# Supply_LDOs.net
KiCad netlist of a schematic drawn in Altium Designer
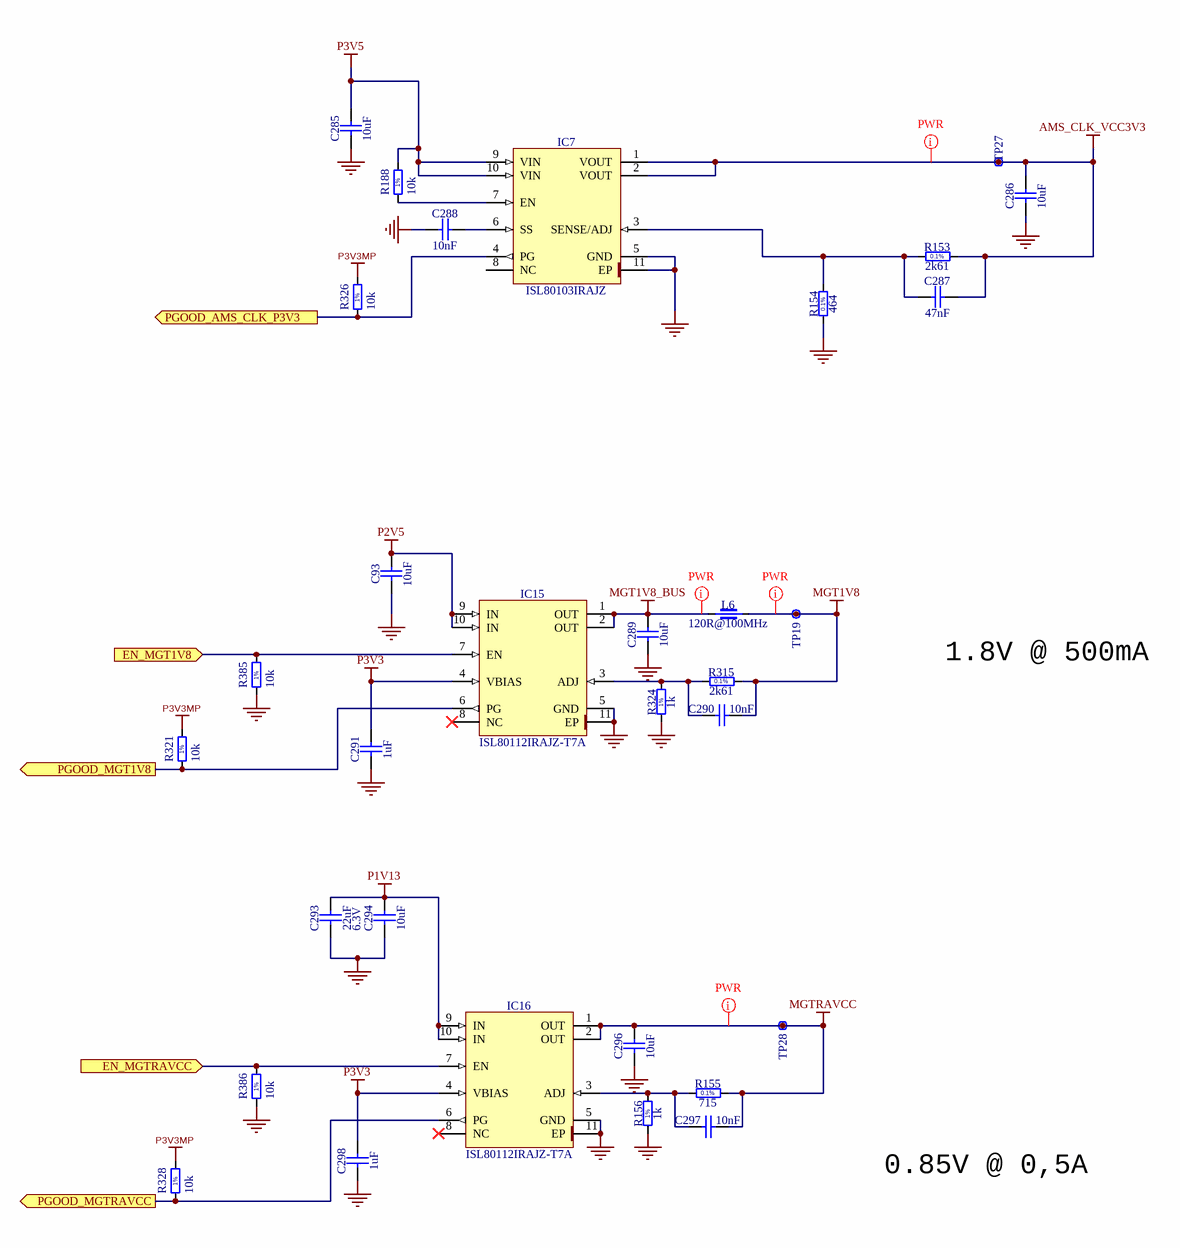
[diagram p0: Supply_LDOs.SchDoc]

(export (version "E")
  (design (tool "Eeschema 10.0.6"))
  (components
    (comp (ref "C93")
      (value "10uF")
      (footprint "CAPC1608X80N")
      (description "Non-polarised capacitor")
      (fields
        (field (name "PART NUMBER") "CC0603_10UF_10V_10%_X5R")
        (field (name "VOLTAGE") "10V")
        (field (name "AUTHOR") "CERN DEM JLC")
      )
      (libsource (lib "Capacitors") (part "Capacitor - non polarized"))
    )
    (comp (ref "C285")
      (value "10uF")
      (footprint "CAPC1608X80N")
      (description "Non-polarised capacitor")
      (fields
        (field (name "PART NUMBER") "CC0603_10UF_10V_10%_X5R")
        (field (name "VOLTAGE") "10V")
        (field (name "AUTHOR") "CERN DEM JLC")
      )
      (libsource (lib "Capacitors") (part "Capacitor - non polarized"))
    )
    (comp (ref "C286")
      (value "10uF")
      (footprint "CAPC1608X80N")
      (description "Non-polarised capacitor")
      (fields
        (field (name "PART NUMBER") "CC0603_10UF_10V_10%_X5R")
        (field (name "VOLTAGE") "10V")
        (field (name "AUTHOR") "CERN DEM JLC")
      )
      (libsource (lib "Capacitors") (part "Capacitor - non polarized"))
    )
    (comp (ref "C287")
      (value "47nF")
      (footprint "CAPC1005X55N")
      (description "Non-polarised capacitor")
      (fields
        (field (name "PART NUMBER") "CC0402_47NF_16V_10%_X7R")
        (field (name "VOLTAGE") "16V")
        (field (name "AUTHOR") "CERN DEM JLC")
      )
      (libsource (lib "Capacitors") (part "Capacitor - non polarized"))
    )
    (comp (ref "C288")
      (value "10nF")
      (footprint "CAPC1005X55N")
      (description "Non-polarised capacitor")
      (fields
        (field (name "PART NUMBER") "CC0402_10NF_16V_10%_X7R")
        (field (name "VOLTAGE") "16V")
        (field (name "AUTHOR") "CERN DEM JLC")
      )
      (libsource (lib "Capacitors") (part "Capacitor - non polarized"))
    )
    (comp (ref "C289")
      (value "10uF")
      (footprint "CAPC1608X80N")
      (description "Non-polarised capacitor")
      (fields
        (field (name "PART NUMBER") "CC0603_10UF_10V_10%_X5R")
        (field (name "VOLTAGE") "10V")
        (field (name "AUTHOR") "CERN DEM JLC")
      )
      (libsource (lib "Capacitors") (part "Capacitor - non polarized"))
    )
    (comp (ref "C290")
      (value "10nF")
      (footprint "CAPC1005X55N")
      (description "Non-polarised capacitor")
      (fields
        (field (name "PART NUMBER") "CC0402_10NF_25V_10%_X7R")
        (field (name "VOLTAGE") "25V")
        (field (name "AUTHOR") "CERN DEM JLC")
      )
      (libsource (lib "Capacitors") (part "Capacitor - non polarized"))
    )
    (comp (ref "C291")
      (value "1uF")
      (footprint "CAPC1005X55N")
      (description "Non-polarised capacitor")
      (fields
        (field (name "PART NUMBER") "CC0402_1UF_16V_10%_X5R")
        (field (name "VOLTAGE") "16V")
        (field (name "AUTHOR") "CERN DEM JLC")
      )
      (libsource (lib "Capacitors") (part "Capacitor - non polarized"))
    )
    (comp (ref "C293")
      (value "22uF")
      (footprint "CAPC1709X100N")
      (description "Non-polarised capacitor")
      (fields
        (field (name "PART NUMBER") "CC0603_22UF_6.3V_20%_X5R")
        (field (name "VOLTAGE") "6.3V")
        (field (name "TOLERANCE") "±20%")
        (field (name "AUTHOR") "CERN DEM JLC")
      )
      (libsource (lib "Capacitors") (part "Capacitor - non polarized"))
    )
    (comp (ref "C294")
      (value "10uF")
      (footprint "CAPC1608X80N")
      (description "Non-polarised capacitor")
      (fields
        (field (name "PART NUMBER") "CC0603_10UF_10V_10%_X5R")
        (field (name "VOLTAGE") "10V")
        (field (name "AUTHOR") "CERN DEM JLC")
      )
      (libsource (lib "Capacitors") (part "Capacitor - non polarized"))
    )
    (comp (ref "C296")
      (value "10uF")
      (footprint "CAPC1608X80N")
      (description "Non-polarised capacitor")
      (fields
        (field (name "PART NUMBER") "CC0603_10UF_10V_10%_X5R")
        (field (name "VOLTAGE") "10V")
        (field (name "AUTHOR") "CERN DEM JLC")
      )
      (libsource (lib "Capacitors") (part "Capacitor - non polarized"))
    )
    (comp (ref "C297")
      (value "10nF")
      (footprint "CAPC1005X55N")
      (description "Non-polarised capacitor")
      (fields
        (field (name "PART NUMBER") "CC0402_10NF_25V_10%_X7R")
        (field (name "VOLTAGE") "25V")
        (field (name "AUTHOR") "CERN DEM JLC")
      )
      (libsource (lib "Capacitors") (part "Capacitor - non polarized"))
    )
    (comp (ref "C298")
      (value "1uF")
      (footprint "CAPC1005X55N")
      (description "Non-polarised capacitor")
      (fields
        (field (name "PART NUMBER") "CC0402_1UF_16V_10%_X5R")
        (field (name "VOLTAGE") "16V")
        (field (name "AUTHOR") "CERN DEM JLC")
      )
      (libsource (lib "Capacitors") (part "Capacitor - non polarized"))
    )
    (comp (ref "IC7")
      (value "ISL80103IRAJZ")
      (footprint "RENESAS_L10.3X3")
      (description "High Performance 3A Linear Regulators")
      (fields (field (name "MANUFACTURER") "RENESAS ELECTRONICS") (field (name "AUTHOR") "CERN DEM MR"))
      (libsource (lib "ICs And Semiconductors") (part "ISL80103"))
    )
    (comp (ref "IC15")
      (value "ISL80112IRAJZ-T7A")
      (footprint "RENESAS_L10.3X3")
      (description "Ultra Low Dropout Low Input Voltage NMOS LDO Regulator")
      (fields (field (name "MANUFACTURER") "RENESAS ELECTRONICS") (field (name "AUTHOR") "CERN DEM JLC"))
      (libsource (lib "ICs And Semiconductors") (part "ISL8011x"))
    )
    (comp (ref "IC16")
      (value "ISL80112IRAJZ-T7A")
      (footprint "RENESAS_L10.3X3")
      (description "Ultra Low Dropout Low Input Voltage NMOS LDO Regulator")
      (fields (field (name "MANUFACTURER") "RENESAS ELECTRONICS") (field (name "AUTHOR") "CERN DEM JLC"))
      (libsource (lib "ICs And Semiconductors") (part "ISL8011x"))
    )
    (comp (ref "L6")
      (value "120R@100MHz")
      (footprint "INDC1608X95N")
      (fields
        (field (name "MANUFACTURER PART NUMBER") "BLM18PG121SN1D")
        (field (name "MANUFACTURER") "MURATA")
        (field (name "PART NUMBER") "IND0603_MURATA_BLM18PG121SN1D")
        (field (name "AUTHOR") "CERN DEM BC")
      )
      (libsource (lib "Inductors & Transformers") (part "Ferrite Bead"))
    )
    (comp (ref "R153")
      (value "2k61")
      (footprint "RESC1608X55N")
      (description "Resistor - 0.1%")
      (fields
        (field (name "PART NUMBER") "R0603_2K61_0.1%_0.063W_10PPM")
        (field (name "POWER") "0.063W")
        (field (name "AUTHOR") "CERN DEM JLC")
      )
      (libsource (lib "Resistors") (part "Resistor - 0.1%"))
    )
    (comp (ref "R154")
      (value "464")
      (footprint "RESC1608X55N")
      (description "Resistor - 0.1%")
      (fields
        (field (name "PART NUMBER") "R0603_464R_0.1%_0.063W_10PPM")
        (field (name "POWER") "0.063W")
        (field (name "AUTHOR") "CERN DEM JLC")
      )
      (libsource (lib "Resistors") (part "Resistor - 0.1%"))
    )
    (comp (ref "R155")
      (value "715")
      (footprint "RESC1608X55N")
      (description "Resistor - 0.1%")
      (fields
        (field (name "PART NUMBER") "R0603_715R_0.1%_0.063W_10PPM")
        (field (name "POWER") "0.063W")
        (field (name "AUTHOR") "CERN DEM JLC")
      )
      (libsource (lib "Resistors") (part "Resistor - 0.1%"))
    )
    (comp (ref "R156")
      (value "1k")
      (footprint "RESC1608X55N")
      (description "Resistor - 1%")
      (fields
        (field (name "PART NUMBER") "R0603_1K_1%_0.1W_100PPM")
        (field (name "POWER") "0.1W")
        (field (name "AUTHOR") "CERN DEM JLC")
      )
      (libsource (lib "Resistors") (part "Resistor - 1%"))
    )
    (comp (ref "R188")
      (value "10k")
      (footprint "RESC1005X40N")
      (description "Resistor - 1%")
      (fields
        (field (name "MANUFACTURER PART NUMBER") "R0402_10K_1%_0.0625W_100PPM")
        (field (name "MANUFACTURER") "GENERIC")
        (field (name "AUTHOR") "CERN DEM JLC")
      )
      (libsource (lib "Resistors") (part "Resistor - 1%"))
    )
    (comp (ref "R315")
      (value "2k61")
      (footprint "RESC1608X55N")
      (description "Resistor - 0.1%")
      (fields
        (field (name "PART NUMBER") "R0603_2K61_0.1%_0.063W_10PPM")
        (field (name "POWER") "0.063W")
        (field (name "AUTHOR") "CERN DEM JLC")
      )
      (libsource (lib "Resistors") (part "Resistor - 0.1%"))
    )
    (comp (ref "R321")
      (value "10k")
      (footprint "RESC1005X40N")
      (description "Resistor - 1%")
      (fields
        (field (name "MANUFACTURER PART NUMBER") "R0402_10K_1%_0.0625W_100PPM")
        (field (name "MANUFACTURER") "GENERIC")
        (field (name "AUTHOR") "CERN DEM JLC")
      )
      (libsource (lib "Resistors") (part "Resistor - 1%"))
    )
    (comp (ref "R324")
      (value "1k")
      (footprint "RESC1608X55N")
      (description "Resistor - 1%")
      (fields
        (field (name "PART NUMBER") "R0603_1K_1%_0.1W_100PPM")
        (field (name "POWER") "0.1W")
        (field (name "AUTHOR") "CERN DEM JLC")
      )
      (libsource (lib "Resistors") (part "Resistor - 1%"))
    )
    (comp (ref "R326")
      (value "10k")
      (footprint "RESC1005X40N")
      (description "Resistor - 1%")
      (fields
        (field (name "MANUFACTURER PART NUMBER") "R0402_10K_1%_0.0625W_100PPM")
        (field (name "MANUFACTURER") "GENERIC")
        (field (name "AUTHOR") "CERN DEM JLC")
      )
      (libsource (lib "Resistors") (part "Resistor - 1%"))
    )
    (comp (ref "R328")
      (value "10k")
      (footprint "RESC1005X40N")
      (description "Resistor - 1%")
      (fields
        (field (name "MANUFACTURER PART NUMBER") "R0402_10K_1%_0.0625W_100PPM")
        (field (name "MANUFACTURER") "GENERIC")
        (field (name "AUTHOR") "CERN DEM JLC")
      )
      (libsource (lib "Resistors") (part "Resistor - 1%"))
    )
    (comp (ref "R385")
      (value "10k")
      (footprint "RESC1005X40N")
      (description "Resistor - 1%")
      (fields
        (field (name "MANUFACTURER PART NUMBER") "R0402_10K_1%_0.0625W_100PPM")
        (field (name "MANUFACTURER") "GENERIC")
        (field (name "AUTHOR") "CERN DEM JLC")
      )
      (libsource (lib "Resistors") (part "Resistor - 1%"))
    )
    (comp (ref "R386")
      (value "10k")
      (footprint "RESC1005X40N")
      (description "Resistor - 1%")
      (fields
        (field (name "MANUFACTURER PART NUMBER") "R0402_10K_1%_0.0625W_100PPM")
        (field (name "MANUFACTURER") "GENERIC")
        (field (name "AUTHOR") "CERN DEM JLC")
      )
      (libsource (lib "Resistors") (part "Resistor - 1%"))
    )
    (comp (ref "TP19")
      (value "Test Point")
      (footprint "TPS127")
      (fields (field (name "PART NUMBER") "SMD_PAD_1.27X1.27MM") (field (name "AUTHOR") "CERN DEM JLC"))
      (libsource (lib "Eletro-mechanical") (part "Test Point"))
    )
    (comp (ref "TP27")
      (value "Test Point")
      (footprint "TPS127")
      (fields (field (name "PART NUMBER") "SMD_PAD_1.27X1.27MM") (field (name "AUTHOR") "CERN DEM JLC"))
      (libsource (lib "Eletro-mechanical") (part "Test Point"))
    )
    (comp (ref "TP28")
      (value "Test Point")
      (footprint "TPS127")
      (fields (field (name "PART NUMBER") "SMD_PAD_1.27X1.27MM") (field (name "AUTHOR") "CERN DEM JLC"))
      (libsource (lib "Eletro-mechanical") (part "Test Point"))
    )
  )
  (nets
    (net (code "1") (name "/EN_MGT1V8") (class "Default")
      (node (ref "IC15") (pin "7") (pinfunction "EN_7") (pintype "input"))
      (node (ref "R385") (pin "2") (pinfunction "2_2") (pintype "passive"))
    )
    (net (code "2") (name "/EN_MGTRAVCC") (class "Default")
      (node (ref "IC16") (pin "7") (pinfunction "EN_7") (pintype "input"))
      (node (ref "R386") (pin "2") (pinfunction "2_2") (pintype "passive"))
    )
    (net (code "3") (name "/PGOOD_AMS_CLK_P3V3") (class "Default")
      (node (ref "IC7") (pin "4") (pinfunction "PG_4") (pintype "output"))
      (node (ref "R326") (pin "1") (pinfunction "1_1") (pintype "passive"))
    )
    (net (code "4") (name "/PGOOD_MGT1V8") (class "Default")
      (node (ref "IC15") (pin "6") (pinfunction "PG_6") (pintype "output"))
      (node (ref "R321") (pin "1") (pinfunction "1_1") (pintype "passive"))
    )
    (net (code "5") (name "/PGOOD_MGTRAVCC") (class "Default")
      (node (ref "IC16") (pin "6") (pinfunction "PG_6") (pintype "output"))
      (node (ref "R328") (pin "1") (pinfunction "1_1") (pintype "passive"))
    )
    (net (code "6") (name "AMS_CLK_VCC3V3") (class "Default")
      (node (ref "C286") (pin "2") (pinfunction "2_2") (pintype "passive"))
      (node (ref "C287") (pin "2") (pinfunction "2_2") (pintype "passive"))
      (node (ref "IC7") (pin "1") (pinfunction "VOUT_1") (pintype "power_in"))
      (node (ref "IC7") (pin "2") (pinfunction "VOUT_2") (pintype "power_in"))
      (node (ref "R153") (pin "2") (pinfunction "2_2") (pintype "passive"))
      (node (ref "TP27") (pin "1") (pinfunction "1_1") (pintype "bidirectional"))
    )
    (net (code "7") (name "GND") (class "Default")
      (node (ref "C285") (pin "1") (pinfunction "1_1") (pintype "passive"))
      (node (ref "C286") (pin "1") (pinfunction "1_1") (pintype "passive"))
      (node (ref "C288") (pin "1") (pinfunction "1_1") (pintype "passive"))
      (node (ref "C289") (pin "1") (pinfunction "1_1") (pintype "passive"))
      (node (ref "C291") (pin "1") (pinfunction "1_1") (pintype "passive"))
      (node (ref "C293") (pin "1") (pinfunction "1_1") (pintype "passive"))
      (node (ref "C294") (pin "1") (pinfunction "1_1") (pintype "passive"))
      (node (ref "C296") (pin "1") (pinfunction "1_1") (pintype "passive"))
      (node (ref "C298") (pin "1") (pinfunction "1_1") (pintype "passive"))
      (node (ref "C93") (pin "1") (pinfunction "1_1") (pintype "passive"))
      (node (ref "IC15") (pin "11") (pinfunction "EP_11") (pintype "power_in"))
      (node (ref "IC15") (pin "5") (pinfunction "GND_5") (pintype "power_in"))
      (node (ref "IC16") (pin "11") (pinfunction "EP_11") (pintype "power_in"))
      (node (ref "IC16") (pin "5") (pinfunction "GND_5") (pintype "power_in"))
      (node (ref "IC7") (pin "11") (pinfunction "EP_11") (pintype "power_in"))
      (node (ref "IC7") (pin "5") (pinfunction "GND_5") (pintype "power_in"))
      (node (ref "R154") (pin "1") (pinfunction "1_1") (pintype "passive"))
      (node (ref "R156") (pin "1") (pinfunction "1_1") (pintype "passive"))
      (node (ref "R324") (pin "1") (pinfunction "1_1") (pintype "passive"))
      (node (ref "R385") (pin "1") (pinfunction "1_1") (pintype "passive"))
      (node (ref "R386") (pin "1") (pinfunction "1_1") (pintype "passive"))
    )
    (net (code "8") (name "MGT1V8") (class "Default")
      (node (ref "C290") (pin "2") (pinfunction "2_2") (pintype "passive"))
      (node (ref "L6") (pin "2") (pinfunction "2_2") (pintype "passive"))
      (node (ref "R315") (pin "2") (pinfunction "2_2") (pintype "passive"))
      (node (ref "TP19") (pin "1") (pinfunction "1_1") (pintype "bidirectional"))
    )
    (net (code "9") (name "MGT1V8_BUS") (class "Default")
      (node (ref "C289") (pin "2") (pinfunction "2_2") (pintype "passive"))
      (node (ref "IC15") (pin "1") (pinfunction "OUT_1") (pintype "power_in"))
      (node (ref "IC15") (pin "2") (pinfunction "OUT_2") (pintype "power_in"))
      (node (ref "L6") (pin "1") (pinfunction "1_1") (pintype "passive"))
    )
    (net (code "10") (name "MGTRAVCC") (class "Default")
      (node (ref "C296") (pin "2") (pinfunction "2_2") (pintype "passive"))
      (node (ref "C297") (pin "2") (pinfunction "2_2") (pintype "passive"))
      (node (ref "IC16") (pin "1") (pinfunction "OUT_1") (pintype "power_in"))
      (node (ref "IC16") (pin "2") (pinfunction "OUT_2") (pintype "power_in"))
      (node (ref "R155") (pin "2") (pinfunction "2_2") (pintype "passive"))
      (node (ref "TP28") (pin "1") (pinfunction "1_1") (pintype "bidirectional"))
    )
    (net (code "11") (name "Net-(IC7-EN)") (class "Default")
      (node (ref "IC7") (pin "7") (pinfunction "EN_7") (pintype "input"))
      (node (ref "R188") (pin "1") (pinfunction "1_1") (pintype "passive"))
    )
    (net (code "12") (name "Net-(IC7-SENSE{slash}ADJ)") (class "Default")
      (node (ref "C287") (pin "1") (pinfunction "1_1") (pintype "passive"))
      (node (ref "IC7") (pin "3") (pinfunction "SENSE/ADJ_3") (pintype "input"))
      (node (ref "R153") (pin "1") (pinfunction "1_1") (pintype "passive"))
      (node (ref "R154") (pin "2") (pinfunction "2_2") (pintype "passive"))
    )
    (net (code "13") (name "Net-(IC7-SS)") (class "Default")
      (node (ref "C288") (pin "2") (pinfunction "2_2") (pintype "passive"))
      (node (ref "IC7") (pin "6") (pinfunction "SS_6") (pintype "input"))
    )
    (net (code "14") (name "Net-(IC15-ADJ)") (class "Default")
      (node (ref "C290") (pin "1") (pinfunction "1_1") (pintype "passive"))
      (node (ref "IC15") (pin "3") (pinfunction "ADJ_3") (pintype "input"))
      (node (ref "R315") (pin "1") (pinfunction "1_1") (pintype "passive"))
      (node (ref "R324") (pin "2") (pinfunction "2_2") (pintype "passive"))
    )
    (net (code "15") (name "Net-(IC16-ADJ)") (class "Default")
      (node (ref "C297") (pin "1") (pinfunction "1_1") (pintype "passive"))
      (node (ref "IC16") (pin "3") (pinfunction "ADJ_3") (pintype "input"))
      (node (ref "R155") (pin "1") (pinfunction "1_1") (pintype "passive"))
      (node (ref "R156") (pin "2") (pinfunction "2_2") (pintype "passive"))
    )
    (net (code "16") (name "P1V13") (class "Default")
      (node (ref "C293") (pin "2") (pinfunction "2_2") (pintype "passive"))
      (node (ref "C294") (pin "2") (pinfunction "2_2") (pintype "passive"))
      (node (ref "IC16") (pin "10") (pinfunction "IN_10") (pintype "input"))
      (node (ref "IC16") (pin "9") (pinfunction "IN_9") (pintype "input"))
    )
    (net (code "17") (name "P2V5") (class "Default")
      (node (ref "C93") (pin "2") (pinfunction "2_2") (pintype "passive"))
      (node (ref "IC15") (pin "10") (pinfunction "IN_10") (pintype "input"))
      (node (ref "IC15") (pin "9") (pinfunction "IN_9") (pintype "input"))
    )
    (net (code "18") (name "P3V3") (class "Default")
      (node (ref "C291") (pin "2") (pinfunction "2_2") (pintype "passive"))
      (node (ref "C298") (pin "2") (pinfunction "2_2") (pintype "passive"))
      (node (ref "IC15") (pin "4") (pinfunction "VBIAS_4") (pintype "input"))
      (node (ref "IC16") (pin "4") (pinfunction "VBIAS_4") (pintype "input"))
    )
    (net (code "19") (name "P3V3MP") (class "Default")
      (node (ref "R321") (pin "2") (pinfunction "2_2") (pintype "passive"))
      (node (ref "R326") (pin "2") (pinfunction "2_2") (pintype "passive"))
      (node (ref "R328") (pin "2") (pinfunction "2_2") (pintype "passive"))
    )
    (net (code "20") (name "P3V5") (class "Default")
      (node (ref "C285") (pin "2") (pinfunction "2_2") (pintype "passive"))
      (node (ref "IC7") (pin "10") (pinfunction "VIN_10") (pintype "input"))
      (node (ref "IC7") (pin "9") (pinfunction "VIN_9") (pintype "input"))
      (node (ref "R188") (pin "2") (pinfunction "2_2") (pintype "passive"))
    )
    (net (code "21") (name "unconnected-(IC7-NC-Pad8)") (class "Default")
      (node (ref "IC7") (pin "8") (pinfunction "NC_8") (pintype "passive"))
    )
    (net (code "22") (name "unconnected-(IC15-NC-Pad8)") (class "Default")
      (node (ref "IC15") (pin "8") (pinfunction "NC_8") (pintype "passive+no_connect"))
    )
    (net (code "23") (name "unconnected-(IC16-NC-Pad8)") (class "Default")
      (node (ref "IC16") (pin "8") (pinfunction "NC_8") (pintype "passive+no_connect"))
    )
  )
)
